# ComparisonSch.net
KiCad netlist of a schematic drawn in Altium Designer
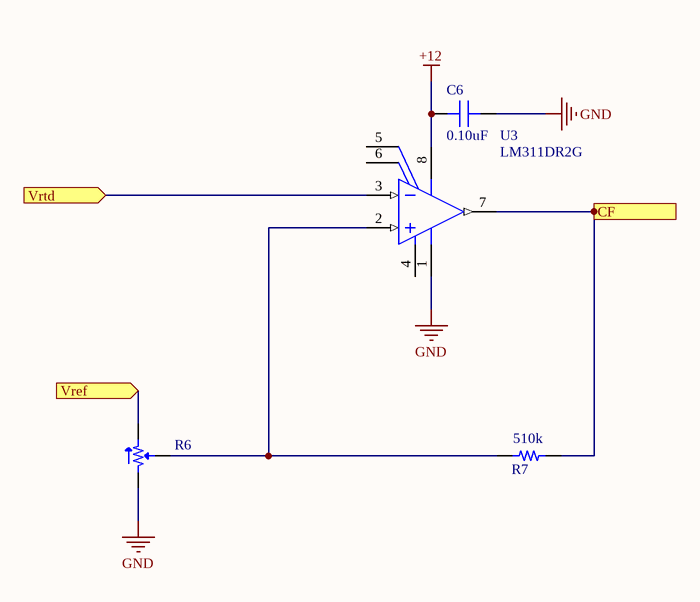
[diagram p0: ComparisonSch.SchDoc]

(export (version "E")
  (design (tool "Eeschema 10.0.6"))
  (components
    (comp (ref "C6")
      (value "0.10uF")
      (footprint "CAP 0402/1005")
      (description "CAP CER 0.1UF 16V X7R 0402")
      (fields
        (field (name "PART NUMBER") "GRM155R71C104JA88D")
        (field (name "MANUFACTURER") "Murata Electronics North America")
      )
      (libsource (lib "Celestial Library Database") (part "Capacitor"))
    )
    (comp (ref "R6")
      (value "20k")
      (footprint "POT MODEL91A")
      (description "TRIMMER 20K OHM 3/8\" CERMET TH")
      (fields (field (name "PART NUMBER") "91AR20KLF") (field (name "MANUFACTURER") "TT Electronics/BI"))
      (libsource (lib "Celestial Library Database") (part "Potentiometer"))
    )
    (comp (ref "R7")
      (value "510k")
      (footprint "RES 1206/3216")
      (description "RES SMD 510K OHM 5% 1/4W 1206")
      (fields
        (field (name "PART NUMBER") "ERJ-8GEYJ514V")
        (field (name "MANUFACTURER") "Panasonic Electronic Components")
      )
      (libsource (lib "Celestial Library Database") (part "Resistor"))
    )
    (comp (ref "U3")
      (value "LM311DR2G")
      (footprint "ONSC-SOIC-8-751-07_V")
      (description "Single Comparator, 5 to 30 V, 0 to 70 degC, 8-Pin SOIC, Pb-Free, Tape and Reel")
      (fields (field (name "MANUFACTURER") "On Semiconductor"))
      (libsource (lib "Altium Content Vault") (part "ONSC-LM211_311-8"))
    )
  )
  (nets
    (net (code "1") (name "+12") (class "Default")
      (node (ref "C6") (pin "1") (pinfunction "1_1") (pintype "passive"))
      (node (ref "U3") (pin "8") (pinfunction "VCC_8") (pintype "power_in"))
    )
    (net (code "2") (name "/CF") (class "Default")
      (node (ref "R7") (pin "2") (pinfunction "2_2") (pintype "passive"))
      (node (ref "U3") (pin "7") (pinfunction "OUT_7") (pintype "output"))
    )
    (net (code "3") (name "/Vref") (class "Default")
      (node (ref "R6") (pin "3") (pinfunction "3_3") (pintype "passive"))
    )
    (net (code "4") (name "/Vrtd") (class "Default")
      (node (ref "U3") (pin "3") (pinfunction "IN-_3") (pintype "input"))
    )
    (net (code "5") (name "GND") (class "Default")
      (node (ref "C6") (pin "2") (pinfunction "2_2") (pintype "passive"))
      (node (ref "R6") (pin "1") (pinfunction "1_1") (pintype "passive"))
      (node (ref "U3") (pin "1") (pinfunction "GND_1") (pintype "power_in"))
    )
    (net (code "6") (name "Net-(U3-IN+)") (class "Default")
      (node (ref "R6") (pin "2") (pinfunction "2_2") (pintype "passive"))
      (node (ref "R7") (pin "1") (pinfunction "1_1") (pintype "passive"))
      (node (ref "U3") (pin "2") (pinfunction "IN+_2") (pintype "input"))
    )
    (net (code "7") (name "unconnected-(U3-BALANCE-Pad5)") (class "Default")
      (node (ref "U3") (pin "5") (pinfunction "BALANCE_5") (pintype "passive"))
    )
    (net (code "8") (name "unconnected-(U3-BALANCE{slash}STROBE-Pad6)") (class "Default")
      (node (ref "U3") (pin "6") (pinfunction "BALANCE/STROBE_6") (pintype "passive"))
    )
    (net (code "9") (name "unconnected-(U3-VEE-Pad4)") (class "Default")
      (node (ref "U3") (pin "4") (pinfunction "VEE_4") (pintype "power_in"))
    )
  )
)
